# RGMII_ETHERNET.net
KiCad netlist of a schematic drawn in Altium Designer
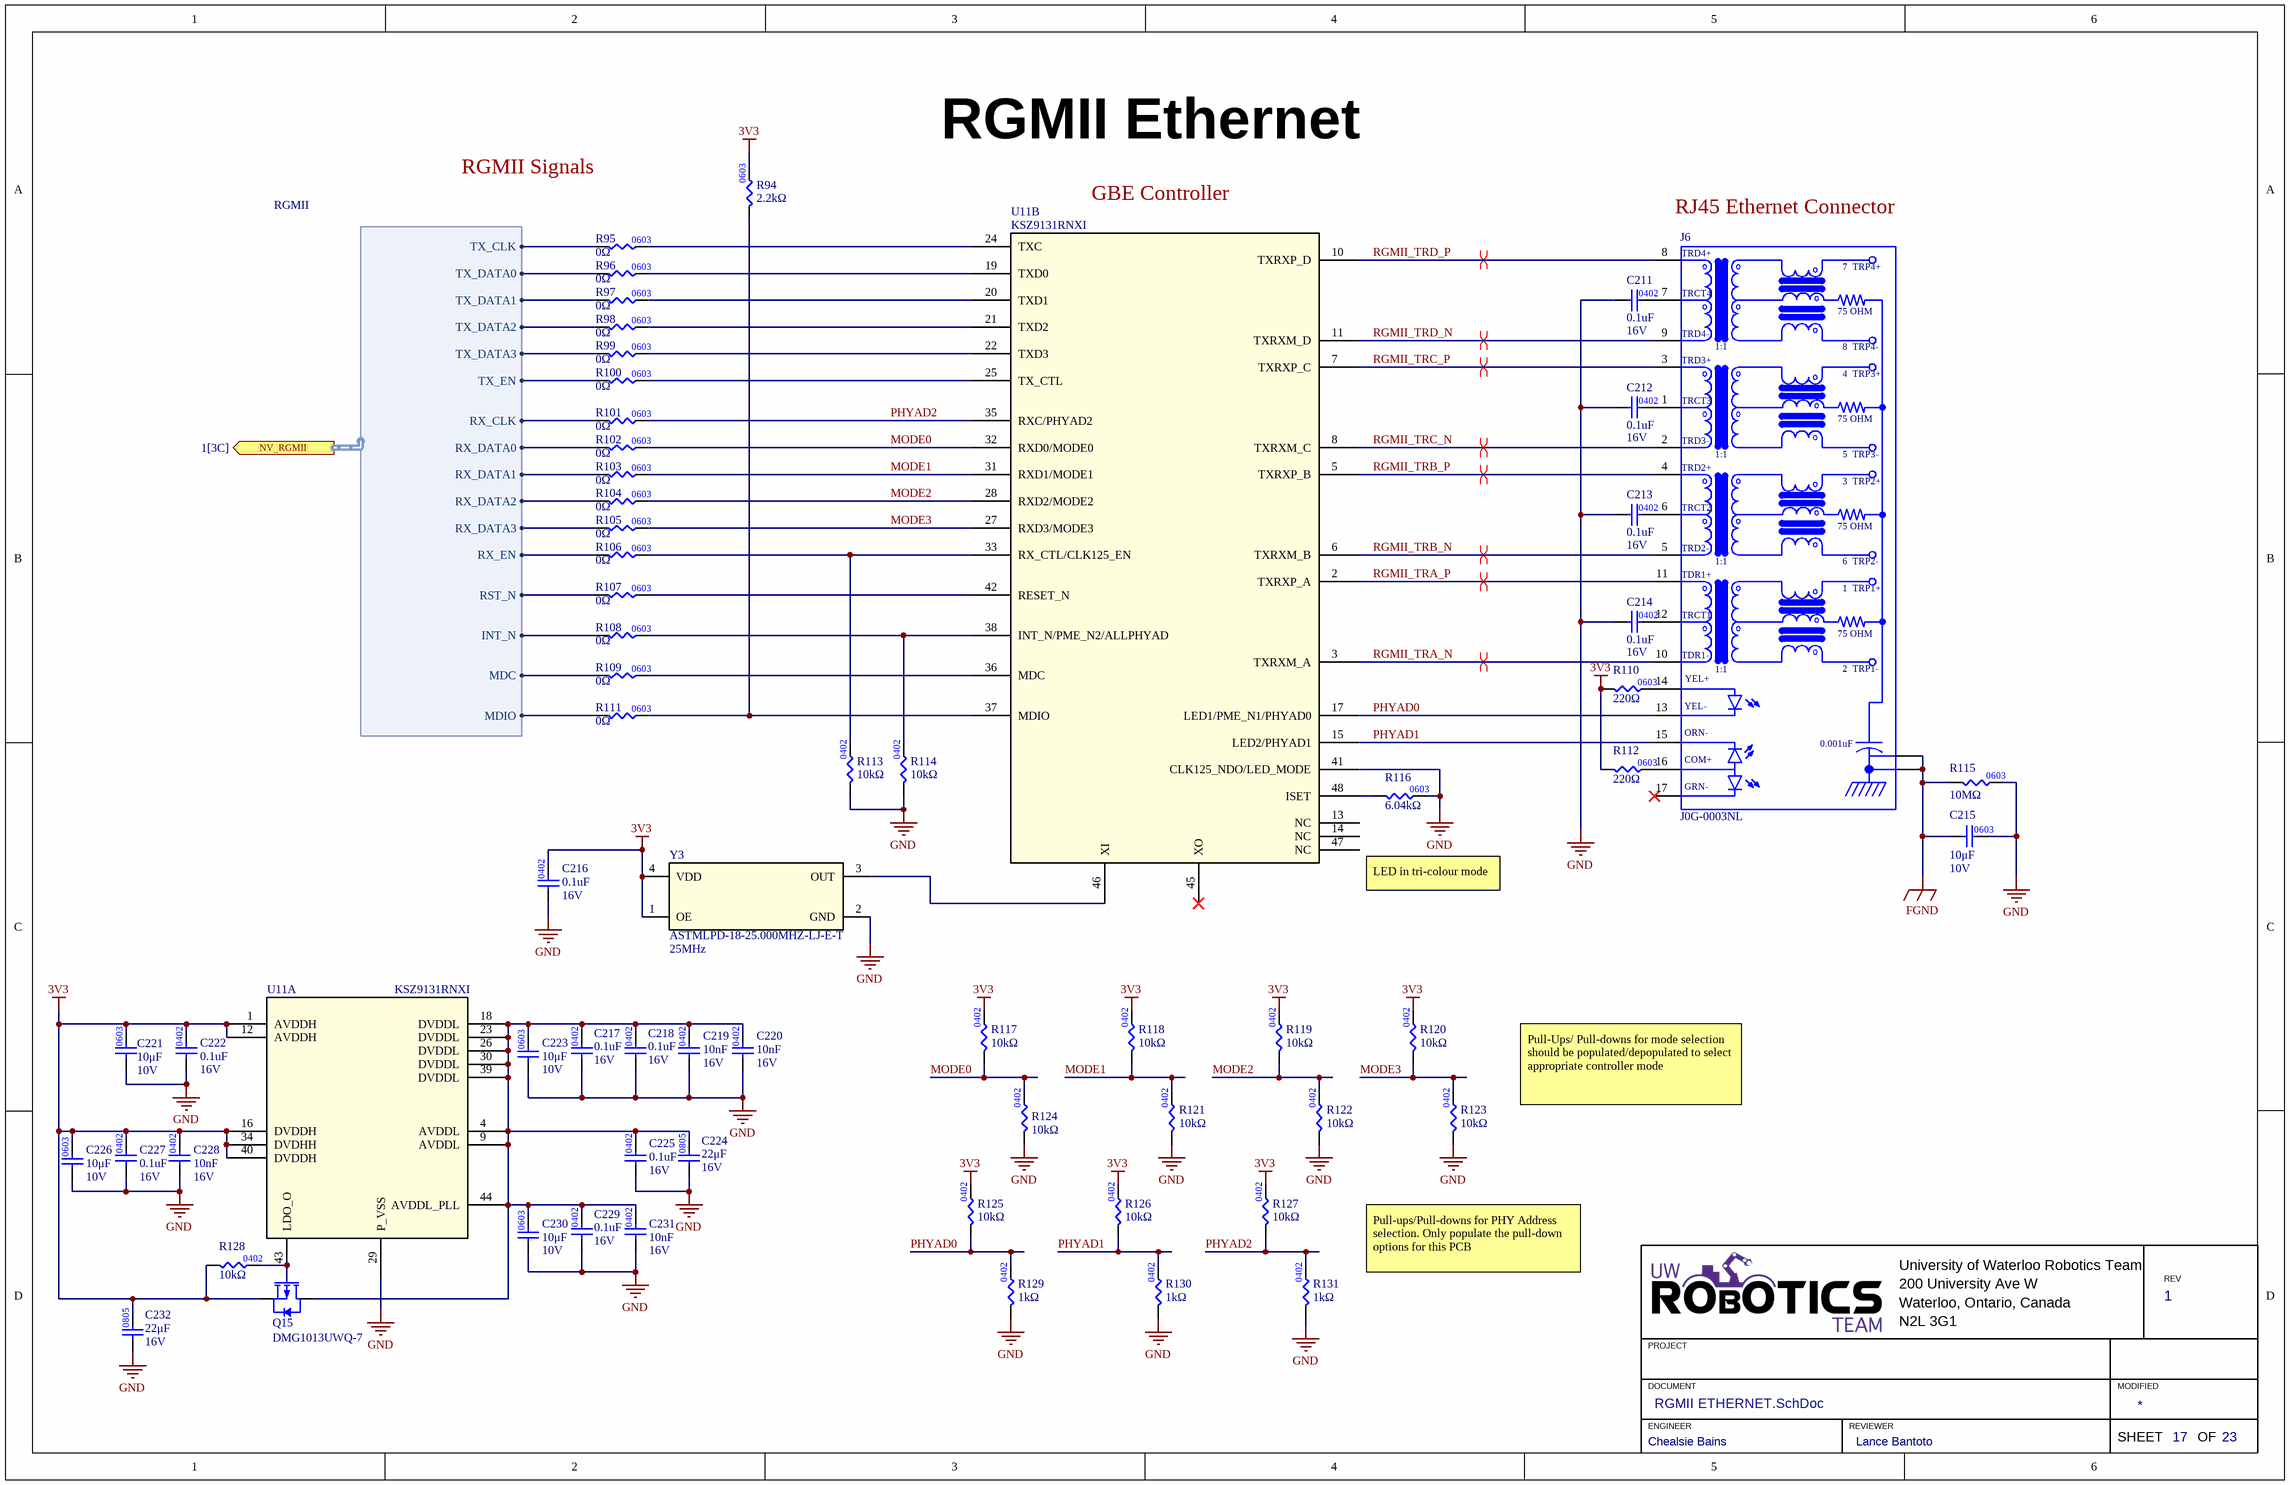
[diagram p0: RGMII ETHERNET.SchDoc]

(export (version "E")
  (design (tool "Eeschema 10.0.6"))
  (components
    (comp (ref "C211")
      (value "CAP_0.1uF_16V_X7R_0402")
      (footprint "CAP0402")
      (description "Ceramic Capacitor, Ceramic")
      (fields
        (field (name "CAPACITANCE") "0.1uF")
        (field (name "MANUFACTURER") "Taiyo Yuden")
        (field (name "MANUFACTURER PART NUMBER") "LMK212AC6106MD-T")
        (field (name "RATED DC VOLTAGE (URDC)") "16V")
      )
      (libsource (lib "UWRT_Schematic_Library_2020") (part "CAP_0.1uF_16V_X7R_0402"))
    )
    (comp (ref "C212")
      (value "CAP_0.1uF_16V_X7R_0402")
      (footprint "CAP0402")
      (description "Ceramic Capacitor, Ceramic")
      (fields
        (field (name "CAPACITANCE") "0.1uF")
        (field (name "MANUFACTURER") "Taiyo Yuden")
        (field (name "MANUFACTURER PART NUMBER") "LMK212AC6106MD-T")
        (field (name "RATED DC VOLTAGE (URDC)") "16V")
      )
      (libsource (lib "UWRT_Schematic_Library_2020") (part "CAP_0.1uF_16V_X7R_0402"))
    )
    (comp (ref "C213")
      (value "CAP_0.1uF_16V_X7R_0402")
      (footprint "CAP0402")
      (description "Ceramic Capacitor, Ceramic")
      (fields
        (field (name "CAPACITANCE") "0.1uF")
        (field (name "MANUFACTURER") "Taiyo Yuden")
        (field (name "MANUFACTURER PART NUMBER") "LMK212AC6106MD-T")
        (field (name "RATED DC VOLTAGE (URDC)") "16V")
      )
      (libsource (lib "UWRT_Schematic_Library_2020") (part "CAP_0.1uF_16V_X7R_0402"))
    )
    (comp (ref "C214")
      (value "CAP_0.1uF_16V_X7R_0402")
      (footprint "CAP0402")
      (description "Ceramic Capacitor, Ceramic")
      (fields
        (field (name "CAPACITANCE") "0.1uF")
        (field (name "MANUFACTURER") "Taiyo Yuden")
        (field (name "MANUFACTURER PART NUMBER") "LMK212AC6106MD-T")
        (field (name "RATED DC VOLTAGE (URDC)") "16V")
      )
      (libsource (lib "UWRT_Schematic_Library_2020") (part "CAP_0.1uF_16V_X7R_0402"))
    )
    (comp (ref "C215")
      (value "10μF")
      (footprint "CAP0603")
      (description "CAP CER 10UF 10V X5R 0603")
      (fields (field (name "VOLTAGE RATING") "10V") (field (name "Comment") "CAP_10uF_10V_0603"))
      (libsource (lib "") (part "CAP_10uF_10V_0603_1"))
    )
    (comp (ref "C216")
      (value "CAP_0.1uF_16V_X7R_0402")
      (footprint "CAP0402")
      (description "Ceramic Capacitor, Ceramic")
      (fields
        (field (name "CAPACITANCE") "0.1uF")
        (field (name "MANUFACTURER") "Taiyo Yuden")
        (field (name "MANUFACTURER PART NUMBER") "LMK212AC6106MD-T")
        (field (name "RATED DC VOLTAGE (URDC)") "16V")
      )
      (libsource (lib "UWRT_Schematic_Library_2020") (part "CAP_0.1uF_16V_X7R_0402"))
    )
    (comp (ref "C217")
      (value "CAP_0.1uF_16V_X7R_0402")
      (footprint "CAP0402")
      (description "Ceramic Capacitor, Ceramic")
      (fields
        (field (name "CAPACITANCE") "0.1uF")
        (field (name "MANUFACTURER") "Taiyo Yuden")
        (field (name "MANUFACTURER PART NUMBER") "LMK212AC6106MD-T")
        (field (name "RATED DC VOLTAGE (URDC)") "16V")
      )
      (libsource (lib "UWRT_Schematic_Library_2020") (part "CAP_0.1uF_16V_X7R_0402"))
    )
    (comp (ref "C218")
      (value "CAP_0.1uF_16V_X7R_0402")
      (footprint "CAP0402")
      (description "Ceramic Capacitor, Ceramic")
      (fields
        (field (name "CAPACITANCE") "0.1uF")
        (field (name "MANUFACTURER") "Taiyo Yuden")
        (field (name "MANUFACTURER PART NUMBER") "LMK212AC6106MD-T")
        (field (name "RATED DC VOLTAGE (URDC)") "16V")
      )
      (libsource (lib "UWRT_Schematic_Library_2020") (part "CAP_0.1uF_16V_X7R_0402"))
    )
    (comp (ref "C219")
      (value "CAP_0.01uF_16V_X7R_0402")
      (footprint "CAP0402")
      (fields
        (field (name "MANUFACTURER") "KEMET")
        (field (name "MANUFACTURER PART NUMBER") "C0402C103J4RACTU")
        (field (name "CAPACITANCE") "10nF")
        (field (name "RATED DC VOLTAGE (URDC)") "16V")
      )
      (libsource (lib "UWRT_Schematic_Library_2020") (part "CAP_0.01uF_16V_X7R_0402"))
    )
    (comp (ref "C220")
      (value "CAP_0.01uF_16V_X7R_0402")
      (footprint "CAP0402")
      (fields
        (field (name "MANUFACTURER") "KEMET")
        (field (name "MANUFACTURER PART NUMBER") "C0402C103J4RACTU")
        (field (name "CAPACITANCE") "10nF")
        (field (name "RATED DC VOLTAGE (URDC)") "16V")
      )
      (libsource (lib "UWRT_Schematic_Library_2020") (part "CAP_0.01uF_16V_X7R_0402"))
    )
    (comp (ref "C221")
      (value "10μF")
      (footprint "CAP0603")
      (description "CAP CER 10UF 10V X5R 0603")
      (fields (field (name "VOLTAGE RATING") "10V") (field (name "Comment") "CAP_10uF_10V_0603"))
      (libsource (lib "UWRT_Schematic_Library_2020") (part "CAP_10uF_10V_0603"))
    )
    (comp (ref "C222")
      (value "CAP_0.1uF_16V_X7R_0402")
      (footprint "CAP0402")
      (description "Ceramic Capacitor, Ceramic")
      (fields
        (field (name "MANUFACTURER") "Taiyo Yuden")
        (field (name "MANUFACTURER PART NUMBER") "LMK212AC6106MD-T")
        (field (name "RATED DC VOLTAGE (URDC)") "16V")
        (field (name "CAPACITANCE") "0.1uF")
      )
      (libsource (lib "UWRT_Schematic_Library_2020") (part "CAP_0.1uF_16V_X7R_0402"))
    )
    (comp (ref "C223")
      (value "10μF")
      (footprint "CAP0603")
      (description "CAP CER 10UF 10V X5R 0603")
      (fields (field (name "VOLTAGE RATING") "10V") (field (name "Comment") "CAP_10uF_10V_0603"))
      (libsource (lib "UWRT_Schematic_Library_2020") (part "CAP_10uF_10V_0603"))
    )
    (comp (ref "C224")
      (value "22μF")
      (footprint "CAP2012")
      (description "CAP CER 22UF 16V X5R 0805")
      (fields (field (name "VOLTAGE RATING") "16V") (field (name "Comment") "CAP_22uF_16V_0805"))
      (libsource (lib "UWRT_Schematic_Library_2020") (part "CAP_22uF_16V_0805"))
    )
    (comp (ref "C225")
      (value "CAP_0.1uF_16V_X7R_0402")
      (footprint "CAP0402")
      (description "Ceramic Capacitor, Ceramic")
      (fields
        (field (name "MANUFACTURER") "Taiyo Yuden")
        (field (name "MANUFACTURER PART NUMBER") "LMK212AC6106MD-T")
        (field (name "RATED DC VOLTAGE (URDC)") "16V")
        (field (name "CAPACITANCE") "0.1uF")
      )
      (libsource (lib "UWRT_Schematic_Library_2020") (part "CAP_0.1uF_16V_X7R_0402"))
    )
    (comp (ref "C226")
      (value "10μF")
      (footprint "CAP0603")
      (description "CAP CER 10UF 10V X5R 0603")
      (fields (field (name "VOLTAGE RATING") "10V") (field (name "Comment") "CAP_10uF_10V_0603"))
      (libsource (lib "UWRT_Schematic_Library_2020") (part "CAP_10uF_10V_0603"))
    )
    (comp (ref "C227")
      (value "CAP_0.1uF_16V_X7R_0402")
      (footprint "CAP0402")
      (description "Ceramic Capacitor, Ceramic")
      (fields
        (field (name "MANUFACTURER") "Taiyo Yuden")
        (field (name "MANUFACTURER PART NUMBER") "LMK212AC6106MD-T")
        (field (name "RATED DC VOLTAGE (URDC)") "16V")
        (field (name "CAPACITANCE") "0.1uF")
      )
      (libsource (lib "UWRT_Schematic_Library_2020") (part "CAP_0.1uF_16V_X7R_0402"))
    )
    (comp (ref "C228")
      (value "CAP_0.01uF_16V_X7R_0402")
      (footprint "CAP0402")
      (fields
        (field (name "MANUFACTURER") "KEMET")
        (field (name "MANUFACTURER PART NUMBER") "C0402C103J4RACTU")
        (field (name "CAPACITANCE") "10nF")
        (field (name "RATED DC VOLTAGE (URDC)") "16V")
      )
      (libsource (lib "UWRT_Schematic_Library_2020") (part "CAP_0.01uF_16V_X7R_0402"))
    )
    (comp (ref "C229")
      (value "CAP_0.1uF_16V_X7R_0402")
      (footprint "CAP0402")
      (description "Ceramic Capacitor, Ceramic")
      (fields
        (field (name "CAPACITANCE") "0.1uF")
        (field (name "MANUFACTURER") "Taiyo Yuden")
        (field (name "MANUFACTURER PART NUMBER") "LMK212AC6106MD-T")
        (field (name "RATED DC VOLTAGE (URDC)") "16V")
      )
      (libsource (lib "UWRT_Schematic_Library_2020") (part "CAP_0.1uF_16V_X7R_0402"))
    )
    (comp (ref "C230")
      (value "10μF")
      (footprint "CAP0603")
      (description "CAP CER 10UF 10V X5R 0603")
      (fields (field (name "VOLTAGE RATING") "10V") (field (name "Comment") "CAP_10uF_10V_0603"))
      (libsource (lib "UWRT_Schematic_Library_2020") (part "CAP_10uF_10V_0603"))
    )
    (comp (ref "C231")
      (value "CAP_0.01uF_16V_X7R_0402")
      (footprint "CAP0402")
      (fields
        (field (name "MANUFACTURER") "KEMET")
        (field (name "MANUFACTURER PART NUMBER") "C0402C103J4RACTU")
        (field (name "CAPACITANCE") "10nF")
        (field (name "RATED DC VOLTAGE (URDC)") "16V")
      )
      (libsource (lib "UWRT_Schematic_Library_2020") (part "CAP_0.01uF_16V_X7R_0402"))
    )
    (comp (ref "C232")
      (value "22μF")
      (footprint "CAP2012")
      (description "CAP CER 22UF 16V X5R 0805")
      (fields (field (name "VOLTAGE RATING") "16V") (field (name "Comment") "CAP_22uF_16V_0805"))
      (libsource (lib "UWRT_Schematic_Library_2020") (part "CAP_22uF_16V_0805"))
    )
    (comp (ref "J6")
      (value "J0G-0003NL")
      (footprint "PULSE_J0G-0003NL")
      (description "1 Port RJ45 Magjack Connector Through Hole 10/100/1000 Base-T, AutoMDIX")
      (fields (field (name "DIGI-KEY_PART_NUMBER") "553-1852-ND") (field (name "MF") "Pulse Electronics"))
      (libsource (lib "UWRT_Schematic_Library_2020") (part "J0G-0003NL"))
    )
    (comp (ref "Q15")
      (value "PMOS_20V_820MA SOT323")
      (fields (field (name "MANUFACTURER") "Diodes") (field (name "MANUFACTURER PART NUMBER") "DMG1013UWQ-7"))
      (libsource (lib "UWRT_Schematic_Library_2020") (part "PMOS_20V_820MA SOT323"))
    )
    (comp (ref "R94")
      (value "2.2kΩ")
      (footprint "RES0603")
      (description "RES 2.2K OHM 1% 1/10W 0603")
      (fields (field (name "Comment") "RES_2.2kΩ_0603_1%"))
      (libsource (lib "UWRT_Schematic_Library_2020") (part "RES_2.2kΩ_0603_1%"))
    )
    (comp (ref "R95")
      (value "0Ω")
      (footprint "RES0603")
      (description "RES 0 OHM JUMPER 1/10W 0603")
      (fields (field (name "Comment") "RES_0Ω_0603"))
      (libsource (lib "UWRT_Schematic_Library_2020") (part "RES_0Ω_0603"))
    )
    (comp (ref "R96")
      (value "0Ω")
      (footprint "RES0603")
      (description "RES 0 OHM JUMPER 1/10W 0603")
      (fields (field (name "Comment") "RES_0Ω_0603"))
      (libsource (lib "UWRT_Schematic_Library_2020") (part "RES_0Ω_0603"))
    )
    (comp (ref "R97")
      (value "0Ω")
      (footprint "RES0603")
      (description "RES 0 OHM JUMPER 1/10W 0603")
      (fields (field (name "Comment") "RES_0Ω_0603"))
      (libsource (lib "UWRT_Schematic_Library_2020") (part "RES_0Ω_0603"))
    )
    (comp (ref "R98")
      (value "0Ω")
      (footprint "RES0603")
      (description "RES 0 OHM JUMPER 1/10W 0603")
      (fields (field (name "Comment") "RES_0Ω_0603"))
      (libsource (lib "UWRT_Schematic_Library_2020") (part "RES_0Ω_0603"))
    )
    (comp (ref "R99")
      (value "0Ω")
      (footprint "RES0603")
      (description "RES 0 OHM JUMPER 1/10W 0603")
      (fields (field (name "Comment") "RES_0Ω_0603"))
      (libsource (lib "UWRT_Schematic_Library_2020") (part "RES_0Ω_0603"))
    )
    (comp (ref "R100")
      (value "0Ω")
      (footprint "RES0603")
      (description "RES 0 OHM JUMPER 1/10W 0603")
      (fields (field (name "Comment") "RES_0Ω_0603"))
      (libsource (lib "UWRT_Schematic_Library_2020") (part "RES_0Ω_0603"))
    )
    (comp (ref "R101")
      (value "0Ω")
      (footprint "RES0603")
      (description "RES 0 OHM JUMPER 1/10W 0603")
      (fields (field (name "Comment") "RES_0Ω_0603"))
      (libsource (lib "UWRT_Schematic_Library_2020") (part "RES_0Ω_0603"))
    )
    (comp (ref "R102")
      (value "0Ω")
      (footprint "RES0603")
      (description "RES 0 OHM JUMPER 1/10W 0603")
      (fields (field (name "Comment") "RES_0Ω_0603"))
      (libsource (lib "UWRT_Schematic_Library_2020") (part "RES_0Ω_0603"))
    )
    (comp (ref "R103")
      (value "0Ω")
      (footprint "RES0603")
      (description "RES 0 OHM JUMPER 1/10W 0603")
      (fields (field (name "Comment") "RES_0Ω_0603"))
      (libsource (lib "UWRT_Schematic_Library_2020") (part "RES_0Ω_0603"))
    )
    (comp (ref "R104")
      (value "0Ω")
      (footprint "RES0603")
      (description "RES 0 OHM JUMPER 1/10W 0603")
      (fields (field (name "Comment") "RES_0Ω_0603"))
      (libsource (lib "UWRT_Schematic_Library_2020") (part "RES_0Ω_0603"))
    )
    (comp (ref "R105")
      (value "0Ω")
      (footprint "RES0603")
      (description "RES 0 OHM JUMPER 1/10W 0603")
      (fields (field (name "Comment") "RES_0Ω_0603"))
      (libsource (lib "UWRT_Schematic_Library_2020") (part "RES_0Ω_0603"))
    )
    (comp (ref "R106")
      (value "0Ω")
      (footprint "RES0603")
      (description "RES 0 OHM JUMPER 1/10W 0603")
      (fields (field (name "Comment") "RES_0Ω_0603"))
      (libsource (lib "UWRT_Schematic_Library_2020") (part "RES_0Ω_0603"))
    )
    (comp (ref "R107")
      (value "0Ω")
      (footprint "RES0603")
      (description "RES 0 OHM JUMPER 1/10W 0603")
      (fields (field (name "Comment") "RES_0Ω_0603"))
      (libsource (lib "UWRT_Schematic_Library_2020") (part "RES_0Ω_0603"))
    )
    (comp (ref "R108")
      (value "0Ω")
      (footprint "RES0603")
      (description "RES 0 OHM JUMPER 1/10W 0603")
      (fields (field (name "Comment") "RES_0Ω_0603"))
      (libsource (lib "UWRT_Schematic_Library_2020") (part "RES_0Ω_0603"))
    )
    (comp (ref "R109")
      (value "0Ω")
      (footprint "RES0603")
      (description "RES 0 OHM JUMPER 1/10W 0603")
      (fields (field (name "Comment") "RES_0Ω_0603"))
      (libsource (lib "UWRT_Schematic_Library_2020") (part "RES_0Ω_0603"))
    )
    (comp (ref "R110")
      (value "220Ω")
      (footprint "RES0603")
      (description "RES 220 OHM 5% 1/10W 0603")
      (fields (field (name "Comment") "RES_220Ω_0603"))
      (libsource (lib "UWRT_Schematic_Library_2020") (part "RES_220Ω_0603_5%"))
    )
    (comp (ref "R111")
      (value "0Ω")
      (footprint "RES0603")
      (description "RES 0 OHM JUMPER 1/10W 0603")
      (fields (field (name "Comment") "RES_0Ω_0603"))
      (libsource (lib "UWRT_Schematic_Library_2020") (part "RES_0Ω_0603"))
    )
    (comp (ref "R112")
      (value "220Ω")
      (footprint "RES0603")
      (description "RES 220 OHM 5% 1/10W 0603")
      (fields (field (name "Comment") "RES_220Ω_0603"))
      (libsource (lib "UWRT_Schematic_Library_2020") (part "RES_220Ω_0603_5%"))
    )
    (comp (ref "R113")
      (value "RES_10kΩ_0402_1%")
      (footprint "RES0402")
      (description "RES 10K OHM 1% 1/16W 0402")
      (fields (field (name "TOLERANCE") "1%") (field (name "RESISTANCE") "10kΩ"))
      (libsource (lib "UWRT_Schematic_Library_2020") (part "RES_10kΩ_0402_1%"))
    )
    (comp (ref "R114")
      (value "RES_10kΩ_0402_1%")
      (footprint "RES0402")
      (description "RES 10K OHM 1% 1/16W 0402")
      (fields (field (name "TOLERANCE") "1%") (field (name "RESISTANCE") "10kΩ"))
      (libsource (lib "UWRT_Schematic_Library_2020") (part "RES_10kΩ_0402_1%"))
    )
    (comp (ref "R115")
      (value "10MΩ")
      (footprint "RES0603")
      (description "RES 10M OHM 5% 1/10W 0603")
      (fields (field (name "Comment") "RES_10MΩ_0603"))
      (libsource (lib "UWRT_Schematic_Library_2020") (part "RES_10MΩ_0603_5%"))
    )
    (comp (ref "R116")
      (value "6.04kΩ")
      (footprint "RES0603")
      (description "RES 6.04K OHM 1% 1/10W 0603")
      (fields (field (name "Comment") "RES_6.04kΩ_0603_1%"))
      (libsource (lib "UWRT_Schematic_Library_2020") (part "RES_6.04kΩ_0603_1%"))
    )
    (comp (ref "R117")
      (value "RES_10kΩ_0402_1%")
      (footprint "RES0402")
      (description "RES 10K OHM 1% 1/16W 0402")
      (fields (field (name "TOLERANCE") "1%") (field (name "RESISTANCE") "10kΩ"))
      (libsource (lib "UWRT_Schematic_Library_2020") (part "RES_10kΩ_0402_1%"))
    )
    (comp (ref "R118")
      (value "RES_10kΩ_0402_1%")
      (footprint "RES0402")
      (description "RES 10K OHM 1% 1/16W 0402")
      (fields (field (name "TOLERANCE") "1%") (field (name "RESISTANCE") "10kΩ"))
      (libsource (lib "UWRT_Schematic_Library_2020") (part "RES_10kΩ_0402_1%"))
    )
    (comp (ref "R119")
      (value "RES_10kΩ_0402_1%")
      (footprint "RES0402")
      (description "RES 10K OHM 1% 1/16W 0402")
      (fields (field (name "TOLERANCE") "1%") (field (name "RESISTANCE") "10kΩ"))
      (libsource (lib "UWRT_Schematic_Library_2020") (part "RES_10kΩ_0402_1%"))
    )
    (comp (ref "R120")
      (value "RES_10kΩ_0402_1%")
      (footprint "RES0402")
      (description "RES 10K OHM 1% 1/16W 0402")
      (fields (field (name "TOLERANCE") "1%") (field (name "RESISTANCE") "10kΩ"))
      (libsource (lib "UWRT_Schematic_Library_2020") (part "RES_10kΩ_0402_1%"))
    )
    (comp (ref "R121")
      (value "RES_10kΩ_0402_1%")
      (footprint "RES0402")
      (description "RES 10K OHM 1% 1/16W 0402")
      (fields (field (name "TOLERANCE") "1%") (field (name "RESISTANCE") "10kΩ"))
      (libsource (lib "UWRT_Schematic_Library_2020") (part "RES_10kΩ_0402_1%"))
    )
    (comp (ref "R122")
      (value "RES_10kΩ_0402_1%")
      (footprint "RES0402")
      (description "RES 10K OHM 1% 1/16W 0402")
      (fields (field (name "TOLERANCE") "1%") (field (name "RESISTANCE") "10kΩ"))
      (libsource (lib "UWRT_Schematic_Library_2020") (part "RES_10kΩ_0402_1%"))
    )
    (comp (ref "R123")
      (value "RES_10kΩ_0402_1%")
      (footprint "RES0402")
      (description "RES 10K OHM 1% 1/16W 0402")
      (fields (field (name "TOLERANCE") "1%") (field (name "RESISTANCE") "10kΩ"))
      (libsource (lib "UWRT_Schematic_Library_2020") (part "RES_10kΩ_0402_1%"))
    )
    (comp (ref "R124")
      (value "RES_10kΩ_0402_1%")
      (footprint "RES0402")
      (description "RES 10K OHM 1% 1/16W 0402")
      (fields (field (name "TOLERANCE") "1%") (field (name "RESISTANCE") "10kΩ"))
      (libsource (lib "UWRT_Schematic_Library_2020") (part "RES_10kΩ_0402_1%"))
    )
    (comp (ref "R125")
      (value "RES_10kΩ_0402_1%")
      (footprint "RES0402")
      (description "RES 10K OHM 1% 1/16W 0402")
      (fields (field (name "TOLERANCE") "1%") (field (name "RESISTANCE") "10kΩ"))
      (libsource (lib "UWRT_Schematic_Library_2020") (part "RES_10kΩ_0402_1%"))
    )
    (comp (ref "R126")
      (value "RES_10kΩ_0402_1%")
      (footprint "RES0402")
      (description "RES 10K OHM 1% 1/16W 0402")
      (fields (field (name "TOLERANCE") "1%") (field (name "RESISTANCE") "10kΩ"))
      (libsource (lib "UWRT_Schematic_Library_2020") (part "RES_10kΩ_0402_1%"))
    )
    (comp (ref "R127")
      (value "RES_10kΩ_0402_1%")
      (footprint "RES0402")
      (description "RES 10K OHM 1% 1/16W 0402")
      (fields (field (name "TOLERANCE") "1%") (field (name "RESISTANCE") "10kΩ"))
      (libsource (lib "UWRT_Schematic_Library_2020") (part "RES_10kΩ_0402_1%"))
    )
    (comp (ref "R128")
      (value "RES_10kΩ_0402")
      (footprint "RES0805")
      (description "Fixed Resistor, Thin Film, 0.1W, 10000ohm, 50V, 0.1% +/-Tol, 25ppm/Cel, Surface Mount, 0402")
      (fields
        (field (name "MANUFACTURER") "Stackpole Electronics")
        (field (name "MANUFACTURER PART NUMBER") "RNCF0402BTE10K0")
        (field (name "RESISTANCE") "10kΩ")
      )
      (libsource (lib "UWRT_Schematic_Library_2020") (part "RES_10kΩ_0402"))
    )
    (comp (ref "R129")
      (value "1kΩ")
      (footprint "RES0402")
      (description "RES 1K OHM 1% 1/16W 0402")
      (fields (field (name "TOLERANCE") "1%") (field (name "Comment") "RES_1kΩ_0402_1%"))
      (libsource (lib "UWRT_Schematic_Library_2020") (part "RES_1kΩ_0402_1%"))
    )
    (comp (ref "R130")
      (value "1kΩ")
      (footprint "RES0402")
      (description "RES 1K OHM 1% 1/16W 0402")
      (fields (field (name "TOLERANCE") "1%") (field (name "Comment") "RES_1kΩ_0402_1%"))
      (libsource (lib "UWRT_Schematic_Library_2020") (part "RES_1kΩ_0402_1%"))
    )
    (comp (ref "R131")
      (value "1kΩ")
      (footprint "RES0402")
      (description "RES 1K OHM 1% 1/16W 0402")
      (fields (field (name "TOLERANCE") "1%") (field (name "Comment") "RES_1kΩ_0402_1%"))
      (libsource (lib "UWRT_Schematic_Library_2020") (part "RES_1kΩ_0402_1%"))
    )
    (comp (ref "U11")
      (value "KSZ9131RNXI")
      (footprint "KSZ9131RNXI")
      (description "Ethernet Transceiver, PQCC48")
      (fields (field (name "MANUFACTURER") "Microchip Technologies"))
      (libsource (lib "") (part "KSZ9131RNXI_1"))
    )
    (comp (ref "Y3")
      (value "ASTMLPD-18-25.000MHZ-LJ-E-T")
      (footprint "ASTMLPE_ABR")
      (description "MEMS OSC XO 25.0000MHZ LVCMOS")
      (fields (field (name "ALTIUM_VALUE") "25MHz"))
      (libsource (lib "UWRT_Schematic_Library_2020") (part "ASTMLPD-18-25.000MHZ-LJ-E-T"))
    )
  )
  (nets
    (net (code "2") (name "/INT_N") (class "Default")
      (node (ref "R108") (pin "1") (pinfunction "1_1") (pintype "passive"))
    )
    (net (code "3") (name "/MDC") (class "Default")
      (node (ref "R109") (pin "1") (pinfunction "1_1") (pintype "passive"))
    )
    (net (code "4") (name "/MDIO") (class "Default")
      (node (ref "R111") (pin "1") (pinfunction "1_1") (pintype "passive"))
    )
    (net (code "5") (name "/MODE0") (class "Default")
      (node (ref "R102") (pin "2") (pinfunction "2_2") (pintype "passive"))
      (node (ref "R117") (pin "1") (pinfunction "1_1") (pintype "passive"))
      (node (ref "R124") (pin "2") (pinfunction "2_2") (pintype "passive"))
      (node (ref "U11") (pin "32") (pinfunction "RXD0/MODE0_32") (pintype "passive"))
    )
    (net (code "6") (name "/MODE1") (class "Default")
      (node (ref "R103") (pin "2") (pinfunction "2_2") (pintype "passive"))
      (node (ref "R118") (pin "1") (pinfunction "1_1") (pintype "passive"))
      (node (ref "R121") (pin "2") (pinfunction "2_2") (pintype "passive"))
      (node (ref "U11") (pin "31") (pinfunction "RXD1/MODE1_31") (pintype "passive"))
    )
    (net (code "7") (name "/MODE2") (class "Default")
      (node (ref "R104") (pin "2") (pinfunction "2_2") (pintype "passive"))
      (node (ref "R119") (pin "1") (pinfunction "1_1") (pintype "passive"))
      (node (ref "R122") (pin "2") (pinfunction "2_2") (pintype "passive"))
      (node (ref "U11") (pin "28") (pinfunction "RXD2/MODE2_28") (pintype "passive"))
    )
    (net (code "8") (name "/MODE3") (class "Default")
      (node (ref "R105") (pin "2") (pinfunction "2_2") (pintype "passive"))
      (node (ref "R120") (pin "1") (pinfunction "1_1") (pintype "passive"))
      (node (ref "R123") (pin "2") (pinfunction "2_2") (pintype "passive"))
      (node (ref "U11") (pin "27") (pinfunction "RXD3/MODE3_27") (pintype "passive"))
    )
    (net (code "9") (name "/PHYAD0") (class "Default")
      (node (ref "J6") (pin "13") (pinfunction "YEL-_13") (pintype "passive"))
      (node (ref "R125") (pin "1") (pinfunction "1_1") (pintype "passive"))
      (node (ref "R129") (pin "2") (pinfunction "2_2") (pintype "passive"))
      (node (ref "U11") (pin "17") (pinfunction "LED1/PME_N1/PHYAD0_17") (pintype "passive"))
    )
    (net (code "10") (name "/PHYAD1") (class "Default")
      (node (ref "J6") (pin "15") (pinfunction "ORN-_15") (pintype "passive"))
      (node (ref "R126") (pin "1") (pinfunction "1_1") (pintype "passive"))
      (node (ref "R130") (pin "2") (pinfunction "2_2") (pintype "passive"))
      (node (ref "U11") (pin "15") (pinfunction "LED2/PHYAD1_15") (pintype "passive"))
    )
    (net (code "11") (name "/PHYAD2") (class "Default")
      (node (ref "R101") (pin "2") (pinfunction "2_2") (pintype "passive"))
      (node (ref "R127") (pin "1") (pinfunction "1_1") (pintype "passive"))
      (node (ref "R131") (pin "2") (pinfunction "2_2") (pintype "passive"))
      (node (ref "U11") (pin "35") (pinfunction "RXC/PHYAD2_35") (pintype "passive"))
    )
    (net (code "12") (name "/RGMII_TRA_N") (class "Default")
      (node (ref "J6") (pin "10") (pinfunction "TDR1-_10") (pintype "passive"))
      (node (ref "U11") (pin "3") (pinfunction "TXRXM_A_3") (pintype "passive"))
    )
    (net (code "13") (name "/RGMII_TRA_P") (class "Default")
      (node (ref "J6") (pin "11") (pinfunction "TDR1+_11") (pintype "passive"))
      (node (ref "U11") (pin "2") (pinfunction "TXRXP_A_2") (pintype "passive"))
    )
    (net (code "14") (name "/RGMII_TRB_N") (class "Default")
      (node (ref "J6") (pin "5") (pinfunction "TRD2-_5") (pintype "passive"))
      (node (ref "U11") (pin "6") (pinfunction "TXRXM_B_6") (pintype "passive"))
    )
    (net (code "15") (name "/RGMII_TRB_P") (class "Default")
      (node (ref "J6") (pin "4") (pinfunction "TRD2+_4") (pintype "passive"))
      (node (ref "U11") (pin "5") (pinfunction "TXRXP_B_5") (pintype "passive"))
    )
    (net (code "16") (name "/RGMII_TRC_N") (class "Default")
      (node (ref "J6") (pin "2") (pinfunction "TRD3-_2") (pintype "passive"))
      (node (ref "U11") (pin "8") (pinfunction "TXRXM_C_8") (pintype "passive"))
    )
    (net (code "17") (name "/RGMII_TRC_P") (class "Default")
      (node (ref "J6") (pin "3") (pinfunction "TRD3+_3") (pintype "passive"))
      (node (ref "U11") (pin "7") (pinfunction "TXRXP_C_7") (pintype "passive"))
    )
    (net (code "18") (name "/RGMII_TRD_N") (class "Default")
      (node (ref "J6") (pin "9") (pinfunction "TRD4-_9") (pintype "passive"))
      (node (ref "U11") (pin "11") (pinfunction "TXRXM_D_11") (pintype "passive"))
    )
    (net (code "19") (name "/RGMII_TRD_P") (class "Default")
      (node (ref "J6") (pin "8") (pinfunction "TRD4+_8") (pintype "passive"))
      (node (ref "U11") (pin "10") (pinfunction "TXRXP_D_10") (pintype "passive"))
    )
    (net (code "20") (name "/RST_N") (class "Default")
      (node (ref "R107") (pin "1") (pinfunction "1_1") (pintype "passive"))
    )
    (net (code "21") (name "/RX_CLK") (class "Default")
      (node (ref "R101") (pin "1") (pinfunction "1_1") (pintype "passive"))
    )
    (net (code "22") (name "/RX_DATA0") (class "Default")
      (node (ref "R102") (pin "1") (pinfunction "1_1") (pintype "passive"))
    )
    (net (code "23") (name "/RX_DATA1") (class "Default")
      (node (ref "R103") (pin "1") (pinfunction "1_1") (pintype "passive"))
    )
    (net (code "24") (name "/RX_DATA2") (class "Default")
      (node (ref "R104") (pin "1") (pinfunction "1_1") (pintype "passive"))
    )
    (net (code "25") (name "/RX_DATA3") (class "Default")
      (node (ref "R105") (pin "1") (pinfunction "1_1") (pintype "passive"))
    )
    (net (code "26") (name "/RX_EN") (class "Default")
      (node (ref "R106") (pin "1") (pinfunction "1_1") (pintype "passive"))
    )
    (net (code "27") (name "/TX_CLK") (class "Default")
      (node (ref "R95") (pin "1") (pinfunction "1_1") (pintype "passive"))
    )
    (net (code "28") (name "/TX_DATA0") (class "Default")
      (node (ref "R96") (pin "1") (pinfunction "1_1") (pintype "passive"))
    )
    (net (code "29") (name "/TX_DATA1") (class "Default")
      (node (ref "R97") (pin "1") (pinfunction "1_1") (pintype "passive"))
    )
    (net (code "30") (name "/TX_DATA2") (class "Default")
      (node (ref "R98") (pin "1") (pinfunction "1_1") (pintype "passive"))
    )
    (net (code "31") (name "/TX_DATA3") (class "Default")
      (node (ref "R99") (pin "1") (pinfunction "1_1") (pintype "passive"))
    )
    (net (code "32") (name "/TX_EN") (class "Default")
      (node (ref "R100") (pin "1") (pinfunction "1_1") (pintype "passive"))
    )
    (net (code "34") (name "3V3") (class "Default")
      (node (ref "C216") (pin "2") (pinfunction "2_2") (pintype "passive"))
      (node (ref "C221") (pin "2") (pinfunction "2_2") (pintype "passive"))
      (node (ref "C222") (pin "2") (pinfunction "2_2") (pintype "passive"))
      (node (ref "C226") (pin "2") (pinfunction "2_2") (pintype "passive"))
      (node (ref "C227") (pin "2") (pinfunction "2_2") (pintype "passive"))
      (node (ref "C228") (pin "2") (pinfunction "2_2") (pintype "passive"))
      (node (ref "C232") (pin "2") (pinfunction "2_2") (pintype "passive"))
      (node (ref "Q15") (pin "3") (pinfunction "Source_3") (pintype "passive"))
      (node (ref "R110") (pin "1") (pinfunction "1_1") (pintype "passive"))
      (node (ref "R112") (pin "1") (pinfunction "1_1") (pintype "passive"))
      (node (ref "R117") (pin "2") (pinfunction "2_2") (pintype "passive"))
      (node (ref "R118") (pin "2") (pinfunction "2_2") (pintype "passive"))
      (node (ref "R119") (pin "2") (pinfunction "2_2") (pintype "passive"))
      (node (ref "R120") (pin "2") (pinfunction "2_2") (pintype "passive"))
      (node (ref "R125") (pin "2") (pinfunction "2_2") (pintype "passive"))
      (node (ref "R126") (pin "2") (pinfunction "2_2") (pintype "passive"))
      (node (ref "R127") (pin "2") (pinfunction "2_2") (pintype "passive"))
      (node (ref "R128") (pin "1") (pinfunction "1_1") (pintype "passive"))
      (node (ref "R94") (pin "2") (pinfunction "2_2") (pintype "passive"))
      (node (ref "U11") (pin "1") (pinfunction "AVDDH_1") (pintype "power_in"))
      (node (ref "U11") (pin "12") (pinfunction "AVDDH_12") (pintype "power_in"))
      (node (ref "U11") (pin "16") (pinfunction "DVDDH_16") (pintype "power_in"))
      (node (ref "U11") (pin "34") (pinfunction "DVDHH_34") (pintype "power_in"))
      (node (ref "U11") (pin "40") (pinfunction "DVDDH_40") (pintype "power_in"))
      (node (ref "Y3") (pin "1") (pinfunction "OE_1") (pintype "passive"))
      (node (ref "Y3") (pin "4") (pinfunction "VDD_4") (pintype "passive"))
    )
    (net (code "35") (name "FGND") (class "Default")
      (node (ref "C215") (pin "1") (pinfunction "1_1") (pintype "passive"))
      (node (ref "J6") (pin "SH1") (pinfunction "SHIELD_SH1") (pintype "power_in"))
      (node (ref "J6") (pin "SH2") (pinfunction "SHIELD_SH2") (pintype "power_in"))
      (node (ref "R115") (pin "1") (pinfunction "1_1") (pintype "passive"))
    )
    (net (code "36") (name "GND") (class "Default")
      (node (ref "C211") (pin "1") (pinfunction "1_1") (pintype "passive"))
      (node (ref "C212") (pin "1") (pinfunction "1_1") (pintype "passive"))
      (node (ref "C213") (pin "1") (pinfunction "1_1") (pintype "passive"))
      (node (ref "C214") (pin "1") (pinfunction "1_1") (pintype "passive"))
      (node (ref "C215") (pin "2") (pinfunction "2_2") (pintype "passive"))
      (node (ref "C216") (pin "1") (pinfunction "1_1") (pintype "passive"))
      (node (ref "C217") (pin "1") (pinfunction "1_1") (pintype "passive"))
      (node (ref "C218") (pin "1") (pinfunction "1_1") (pintype "passive"))
      (node (ref "C219") (pin "1") (pinfunction "1_1") (pintype "passive"))
      (node (ref "C220") (pin "1") (pinfunction "1_1") (pintype "passive"))
      (node (ref "C221") (pin "1") (pinfunction "1_1") (pintype "passive"))
      (node (ref "C222") (pin "1") (pinfunction "1_1") (pintype "passive"))
      (node (ref "C223") (pin "1") (pinfunction "1_1") (pintype "passive"))
      (node (ref "C224") (pin "1") (pinfunction "1_1") (pintype "passive"))
      (node (ref "C225") (pin "1") (pinfunction "1_1") (pintype "passive"))
      (node (ref "C226") (pin "1") (pinfunction "1_1") (pintype "passive"))
      (node (ref "C227") (pin "1") (pinfunction "1_1") (pintype "passive"))
      (node (ref "C228") (pin "1") (pinfunction "1_1") (pintype "passive"))
      (node (ref "C229") (pin "1") (pinfunction "1_1") (pintype "passive"))
      (node (ref "C230") (pin "1") (pinfunction "1_1") (pintype "passive"))
      (node (ref "C231") (pin "1") (pinfunction "1_1") (pintype "passive"))
      (node (ref "C232") (pin "1") (pinfunction "1_1") (pintype "passive"))
      (node (ref "R113") (pin "1") (pinfunction "1_1") (pintype "passive"))
      (node (ref "R114") (pin "1") (pinfunction "1_1") (pintype "passive"))
      (node (ref "R115") (pin "2") (pinfunction "2_2") (pintype "passive"))
      (node (ref "R116") (pin "2") (pinfunction "2_2") (pintype "passive"))
      (node (ref "R121") (pin "1") (pinfunction "1_1") (pintype "passive"))
      (node (ref "R122") (pin "1") (pinfunction "1_1") (pintype "passive"))
      (node (ref "R123") (pin "1") (pinfunction "1_1") (pintype "passive"))
      (node (ref "R124") (pin "1") (pinfunction "1_1") (pintype "passive"))
      (node (ref "R129") (pin "1") (pinfunction "1_1") (pintype "passive"))
      (node (ref "R130") (pin "1") (pinfunction "1_1") (pintype "passive"))
      (node (ref "R131") (pin "1") (pinfunction "1_1") (pintype "passive"))
      (node (ref "U11") (pin "29") (pinfunction "P_VSS_29") (pintype "power_in"))
      (node (ref "U11") (pin "41") (pinfunction "CLK125_NDO/LED_MODE_41") (pintype "passive"))
      (node (ref "Y3") (pin "2") (pinfunction "GND_2") (pintype "passive"))
    )
    (net (code "37") (name "Net-(J6-COM+)") (class "Default")
      (node (ref "J6") (pin "16") (pinfunction "COM+_16") (pintype "passive"))
      (node (ref "R112") (pin "2") (pinfunction "2_2") (pintype "passive"))
    )
    (net (code "38") (name "Net-(J6-TRCT1)") (class "Default")
      (node (ref "C214") (pin "2") (pinfunction "2_2") (pintype "passive"))
      (node (ref "J6") (pin "12") (pinfunction "TRCT1_12") (pintype "passive"))
    )
    (net (code "39") (name "Net-(J6-TRCT2)") (class "Default")
      (node (ref "C213") (pin "2") (pinfunction "2_2") (pintype "passive"))
      (node (ref "J6") (pin "6") (pinfunction "TRCT2_6") (pintype "passive"))
    )
    (net (code "40") (name "Net-(J6-TRCT3)") (class "Default")
      (node (ref "C212") (pin "2") (pinfunction "2_2") (pintype "passive"))
      (node (ref "J6") (pin "1") (pinfunction "TRCT3_1") (pintype "passive"))
    )
    (net (code "41") (name "Net-(J6-TRCT4)") (class "Default")
      (node (ref "C211") (pin "2") (pinfunction "2_2") (pintype "passive"))
      (node (ref "J6") (pin "7") (pinfunction "TRCT4_7") (pintype "passive"))
    )
    (net (code "42") (name "Net-(J6-YEL+)") (class "Default")
      (node (ref "J6") (pin "14") (pinfunction "YEL+_14") (pintype "passive"))
      (node (ref "R110") (pin "2") (pinfunction "2_2") (pintype "passive"))
    )
    (net (code "43") (name "Net-(Q15-Drain)") (class "Default")
      (node (ref "C217") (pin "2") (pinfunction "2_2") (pintype "passive"))
      (node (ref "C218") (pin "2") (pinfunction "2_2") (pintype "passive"))
      (node (ref "C219") (pin "2") (pinfunction "2_2") (pintype "passive"))
      (node (ref "C220") (pin "2") (pinfunction "2_2") (pintype "passive"))
      (node (ref "C223") (pin "2") (pinfunction "2_2") (pintype "passive"))
      (node (ref "C224") (pin "2") (pinfunction "2_2") (pintype "passive"))
      (node (ref "C225") (pin "2") (pinfunction "2_2") (pintype "passive"))
      (node (ref "C229") (pin "2") (pinfunction "2_2") (pintype "passive"))
      (node (ref "C230") (pin "2") (pinfunction "2_2") (pintype "passive"))
      (node (ref "C231") (pin "2") (pinfunction "2_2") (pintype "passive"))
      (node (ref "Q15") (pin "1") (pinfunction "Drain_1") (pintype "passive"))
      (node (ref "U11") (pin "18") (pinfunction "DVDDL_18") (pintype "power_in"))
      (node (ref "U11") (pin "23") (pinfunction "DVDDL_23") (pintype "power_in"))
      (node (ref "U11") (pin "26") (pinfunction "DVDDL_26") (pintype "power_in"))
      (node (ref "U11") (pin "30") (pinfunction "DVDDL_30") (pintype "power_in"))
      (node (ref "U11") (pin "39") (pinfunction "DVDDL_39") (pintype "power_in"))
      (node (ref "U11") (pin "4") (pinfunction "AVDDL_4") (pintype "power_in"))
      (node (ref "U11") (pin "44") (pinfunction "AVDDL_PLL_44") (pintype "power_in"))
      (node (ref "U11") (pin "9") (pinfunction "AVDDL_9") (pintype "power_in"))
    )
    (net (code "44") (name "Net-(Q15-Gate)") (class "Default")
      (node (ref "Q15") (pin "2") (pinfunction "Gate_2") (pintype "passive"))
      (node (ref "R128") (pin "2") (pinfunction "2_2") (pintype "passive"))
      (node (ref "U11") (pin "43") (pinfunction "LDO_O_43") (pintype "power_in"))
    )
    (net (code "45") (name "Net-(U11B-INT_N{slash}PME_N2{slash}ALLPHYAD)") (class "Default")
      (node (ref "R108") (pin "2") (pinfunction "2_2") (pintype "passive"))
      (node (ref "R114") (pin "2") (pinfunction "2_2") (pintype "passive"))
      (node (ref "U11") (pin "38") (pinfunction "INT_N/PME_N2/ALLPHYAD_38") (pintype "passive"))
    )
    (net (code "46") (name "Net-(U11B-ISET)") (class "Default")
      (node (ref "R116") (pin "1") (pinfunction "1_1") (pintype "passive"))
      (node (ref "U11") (pin "48") (pinfunction "ISET_48") (pintype "passive"))
    )
    (net (code "47") (name "Net-(U11B-MDC)") (class "Default")
      (node (ref "R109") (pin "2") (pinfunction "2_2") (pintype "passive"))
      (node (ref "U11") (pin "36") (pinfunction "MDC_36") (pintype "passive"))
    )
    (net (code "48") (name "Net-(U11B-MDIO)") (class "Default")
      (node (ref "R111") (pin "2") (pinfunction "2_2") (pintype "passive"))
      (node (ref "R94") (pin "1") (pinfunction "1_1") (pintype "passive"))
      (node (ref "U11") (pin "37") (pinfunction "MDIO_37") (pintype "passive"))
    )
    (net (code "49") (name "Net-(U11B-RESET_N)") (class "Default")
      (node (ref "R107") (pin "2") (pinfunction "2_2") (pintype "passive"))
      (node (ref "U11") (pin "42") (pinfunction "RESET_N_42") (pintype "passive"))
    )
    (net (code "50") (name "Net-(U11B-RX_CTL{slash}CLK125_EN)") (class "Default")
      (node (ref "R106") (pin "2") (pinfunction "2_2") (pintype "passive"))
      (node (ref "R113") (pin "2") (pinfunction "2_2") (pintype "passive"))
      (node (ref "U11") (pin "33") (pinfunction "RX_CTL/CLK125_EN_33") (pintype "passive"))
    )
    (net (code "51") (name "Net-(U11B-TXC)") (class "Default")
      (node (ref "R95") (pin "2") (pinfunction "2_2") (pintype "passive"))
      (node (ref "U11") (pin "24") (pinfunction "TXC_24") (pintype "passive"))
    )
    (net (code "52") (name "Net-(U11B-TXD0)") (class "Default")
      (node (ref "R96") (pin "2") (pinfunction "2_2") (pintype "passive"))
      (node (ref "U11") (pin "19") (pinfunction "TXD0_19") (pintype "passive"))
    )
    (net (code "53") (name "Net-(U11B-TXD1)") (class "Default")
      (node (ref "R97") (pin "2") (pinfunction "2_2") (pintype "passive"))
      (node (ref "U11") (pin "20") (pinfunction "TXD1_20") (pintype "passive"))
    )
    (net (code "54") (name "Net-(U11B-TXD2)") (class "Default")
      (node (ref "R98") (pin "2") (pinfunction "2_2") (pintype "passive"))
      (node (ref "U11") (pin "21") (pinfunction "TXD2_21") (pintype "passive"))
    )
    (net (code "55") (name "Net-(U11B-TXD3)") (class "Default")
      (node (ref "R99") (pin "2") (pinfunction "2_2") (pintype "passive"))
      (node (ref "U11") (pin "22") (pinfunction "TXD3_22") (pintype "passive"))
    )
    (net (code "56") (name "Net-(U11B-TX_CTL)") (class "Default")
      (node (ref "R100") (pin "2") (pinfunction "2_2") (pintype "passive"))
      (node (ref "U11") (pin "25") (pinfunction "TX_CTL_25") (pintype "passive"))
    )
    (net (code "57") (name "Net-(U11B-XI)") (class "Default")
      (node (ref "U11") (pin "46") (pinfunction "XI_46") (pintype "passive"))
      (node (ref "Y3") (pin "3") (pinfunction "OUT_3") (pintype "passive"))
    )
    (net (code "58") (name "unconnected-(J6-GRN--Pad17)") (class "Default")
      (node (ref "J6") (pin "17") (pinfunction "GRN-_17") (pintype "passive+no_connect"))
    )
    (net (code "59") (name "unconnected-(U11B-NC-Pad13)") (class "Default")
      (node (ref "U11") (pin "13") (pinfunction "NC_13") (pintype "passive"))
    )
    (net (code "60") (name "unconnected-(U11B-NC-Pad14)") (class "Default")
      (node (ref "U11") (pin "14") (pinfunction "NC_14") (pintype "passive"))
    )
    (net (code "61") (name "unconnected-(U11B-NC-Pad47)") (class "Default")
      (node (ref "U11") (pin "47") (pinfunction "NC_47") (pintype "passive"))
    )
    (net (code "62") (name "unconnected-(U11B-XO-Pad45)") (class "Default")
      (node (ref "U11") (pin "45") (pinfunction "XO_45") (pintype "passive+no_connect"))
    )
  )
)
